# schematic.net
KiCad netlist of a schematic drawn in EasyEDA
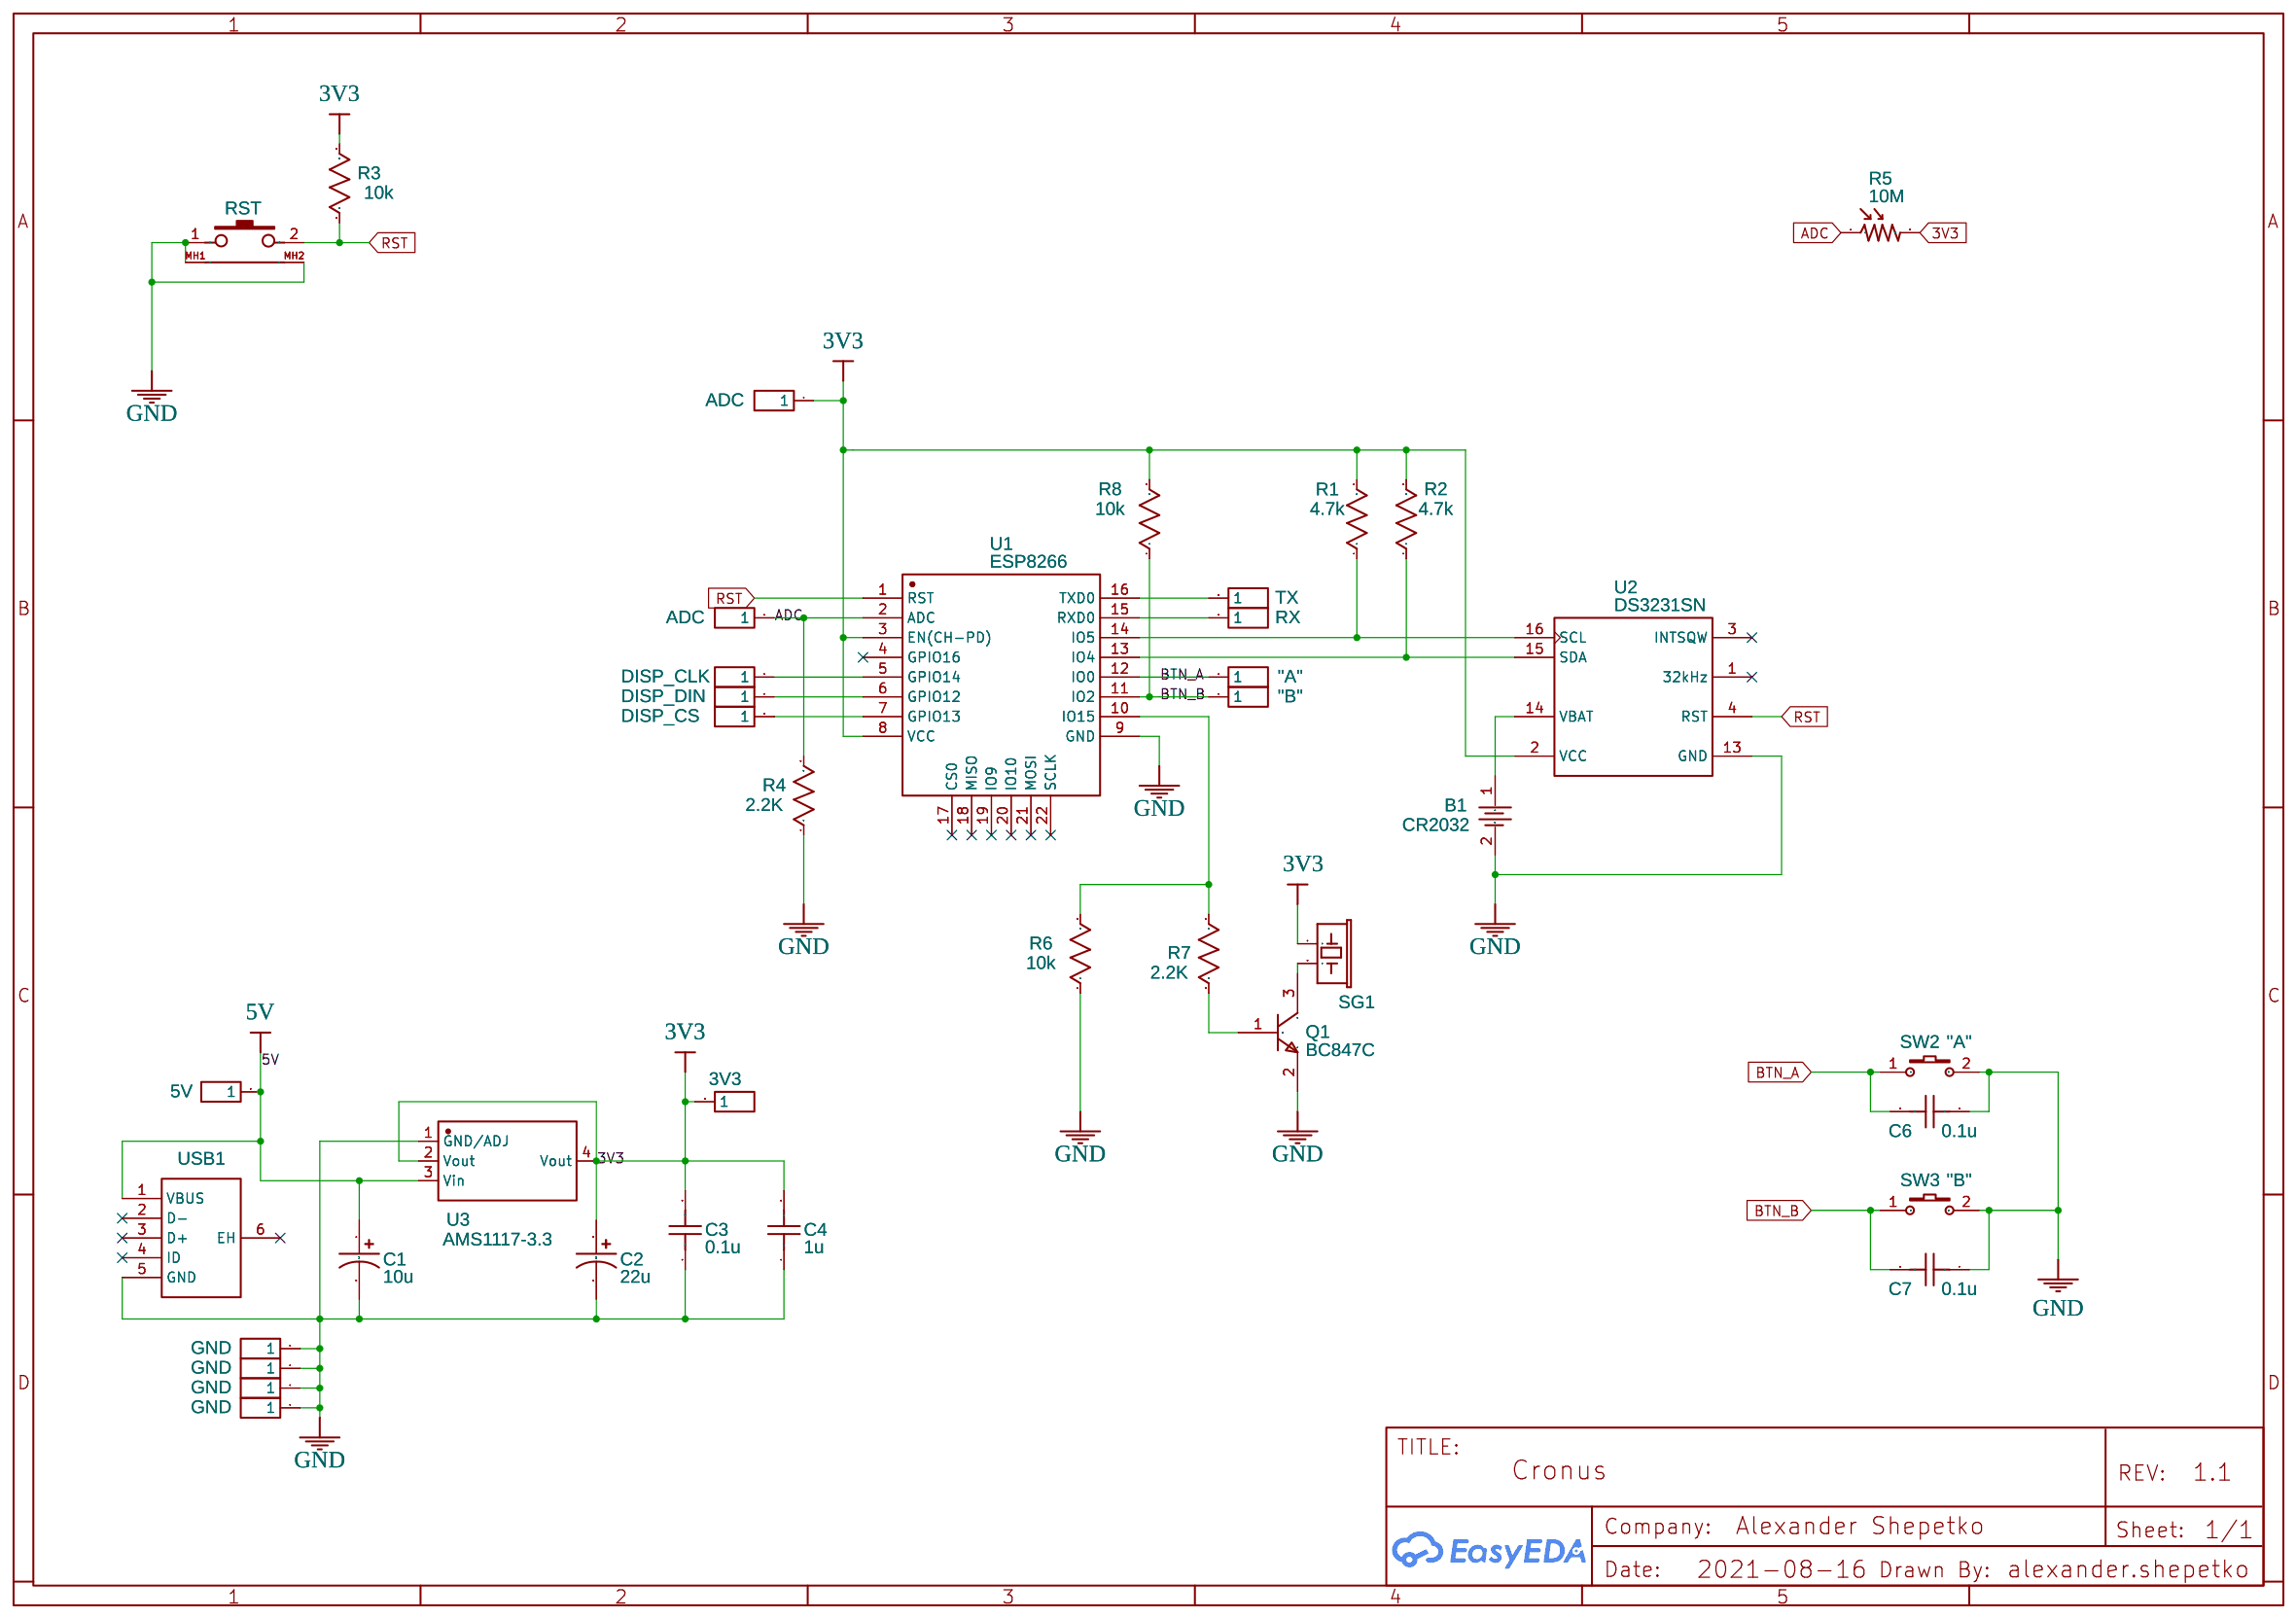
[diagram p0: schematic sheet]

(export (version "E")
  (design (tool "Eeschema 10.0.6"))
  (components
    (comp (ref "B1")
      (value "CR2032")
      (fields (field (name "BOM_Manufacturer Part") "BS-2-1") (field (name "BOM_Supplier Part") "C70376"))
      (libsource (lib "") (part "CR2032-BS-2-1"))
    )
    (comp (ref "C1") (value "10u") (libsource (lib "") (part "C_Tan_SMD_A_US_1")))
    (comp (ref "C2") (value "22u") (libsource (lib "") (part "C_Tan_SMD_A_US")))
    (comp (ref "C3") (value "0.1u") (libsource (lib "") (part "C_0603_US")))
    (comp (ref "C4") (value "1u") (libsource (lib "") (part "C_0603_US")))
    (comp (ref "C6") (value "0.1u") (libsource (lib "") (part "C_0603_US_1")))
    (comp (ref "C7") (value "0.1u") (libsource (lib "") (part "C_0603_US_1")))
    (comp (ref "J1")
      (value "DISP_CLK")
      (fields (field (name "BOM_Supplier Part") "C81276"))
      (libsource (lib "") (part "HDR-M-2.54_1x1_1"))
    )
    (comp (ref "J2")
      (value "DISP_DIN")
      (fields (field (name "BOM_Supplier Part") "C81276"))
      (libsource (lib "") (part "HDR-M-2.54_1x1_1"))
    )
    (comp (ref "J3")
      (value "DISP_CS")
      (fields (field (name "BOM_Supplier Part") "C81276"))
      (libsource (lib "") (part "HDR-M-2.54_1x1_1"))
    )
    (comp (ref "J4")
      (value "\"A\"")
      (fields (field (name "BOM_Supplier Part") "C81276"))
      (libsource (lib "") (part "HDR-M-2.54_1x1"))
    )
    (comp (ref "J5")
      (value "TX")
      (fields (field (name "BOM_Supplier Part") "C81276"))
      (libsource (lib "") (part "HDR-M-2.54_1x1"))
    )
    (comp (ref "J6")
      (value "RX")
      (fields (field (name "BOM_Supplier Part") "C81276"))
      (libsource (lib "") (part "HDR-M-2.54_1x1"))
    )
    (comp (ref "J7")
      (value "\"B\"")
      (fields (field (name "BOM_Supplier Part") "C81276"))
      (libsource (lib "") (part "HDR-M-2.54_1x1"))
    )
    (comp (ref "J8")
      (value "ADC")
      (fields (field (name "BOM_Supplier Part") "C81276"))
      (libsource (lib "") (part "HDR-M-2.54_1x1_1"))
    )
    (comp (ref "J9")
      (value "GND")
      (fields (field (name "BOM_Supplier Part") "C81276"))
      (libsource (lib "") (part "HDR-M-2.54_1x1_1"))
    )
    (comp (ref "J10")
      (value "ADC")
      (fields (field (name "BOM_Supplier Part") "C81276"))
      (libsource (lib "") (part "HDR-M-2.54_1x1_1"))
    )
    (comp (ref "J11")
      (value "GND")
      (fields (field (name "BOM_Supplier Part") "C81276"))
      (libsource (lib "") (part "HDR-M-2.54_1x1_1"))
    )
    (comp (ref "J12")
      (value "5V")
      (fields (field (name "BOM_Supplier Part") "C81276"))
      (libsource (lib "") (part "HDR-M-2.54_1x1_1"))
    )
    (comp (ref "J13")
      (value "GND")
      (fields (field (name "BOM_Supplier Part") "C81276"))
      (libsource (lib "") (part "HDR-M-2.54_1x1_1"))
    )
    (comp (ref "J14")
      (value "GND")
      (fields (field (name "BOM_Supplier Part") "C81276"))
      (libsource (lib "") (part "HDR-M-2.54_1x1_1"))
    )
    (comp (ref "J15")
      (value "3V3")
      (fields (field (name "BOM_Supplier Part") "C81276"))
      (libsource (lib "") (part "HDR-M-2.54_1x1"))
    )
    (comp (ref "Q1") (value "BC847C") (libsource (lib "") (part "BC847CLT3")))
    (comp (ref "R1") (value "4.7k") (libsource (lib "") (part "R_0603_US")))
    (comp (ref "R2") (value "4.7k") (libsource (lib "") (part "R_0603_US")))
    (comp (ref "R3") (value "10k") (libsource (lib "") (part "R_0603_US")))
    (comp (ref "R4") (value "2.2K") (libsource (lib "") (part "R_0603_US")))
    (comp (ref "R5") (value "10M") (libsource (lib "") (part "PHOTORESPDV-P9")))
    (comp (ref "R6") (value "10k") (libsource (lib "") (part "R_0603_US")))
    (comp (ref "R7") (value "2.2K") (libsource (lib "") (part "R_0603_US_1")))
    (comp (ref "R8") (value "10k") (libsource (lib "") (part "R_0603_US")))
    (comp (ref "SG1") (value "BUZZER") (libsource (lib "") (part "BUZZER")))
    (comp (ref "SW1")
      (value "RST")
      (fields
        (field (name "BOM_Manufacturer Part") "Switch,6*6*9Plastic head,260G, 0.25mm,Side bracket")
        (field (name "BOM_Supplier Part") "C71842")
      )
      (libsource (lib "") (part "Button-6x6x9-Right-Angle"))
    )
    (comp (ref "SW2")
      (value "\"A\"")
      (fields
        (field (name "BOM_Manufacturer Part") "K2-1107ST-A4SW-06")
        (field (name "BOM_Supplier Part") "C118141")
      )
      (libsource (lib "") (part "K2-3.6×6.1_SMD"))
    )
    (comp (ref "SW3")
      (value "\"B\"")
      (fields
        (field (name "BOM_Manufacturer Part") "K2-1107ST-A4SW-06")
        (field (name "BOM_Supplier Part") "C118141")
      )
      (libsource (lib "") (part "K2-3.6×6.1_SMD"))
    )
    (comp (ref "U1")
      (value "ESP8266")
      (fields
        (field (name "BOM_Manufacturer Part") "ESP-12F(ESP8266MOD)")
        (field (name "BOM_Supplier Part") "C82891")
      )
      (libsource (lib "") (part "ESP-12F(ESP8266MOD)"))
    )
    (comp (ref "U2")
      (value "DS3231SN")
      (fields (field (name "BOM_Supplier Part") "C9866"))
      (libsource (lib "") (part "DS3231SN#"))
    )
    (comp (ref "U3")
      (value "AMS1117-3.3")
      (fields (field (name "BOM_Supplier Part") "C6186"))
      (libsource (lib "") (part "AMS1117-3.3"))
    )
    (comp (ref "USB1")
      (value "A4A0505-C-30-R")
      (fields (field (name "BOM_Supplier Part") "C694908"))
      (libsource (lib "") (part "A4A0505-C-30-R"))
    )
  )
  (nets
    (net (code "1") (name "3V3") (class "Default")
      (node (ref "C2") (pin "2") (pinfunction "1_2") (pintype "unspecified"))
      (node (ref "C3") (pin "2") (pinfunction "2_2") (pintype "unspecified"))
      (node (ref "C4") (pin "2") (pinfunction "2_2") (pintype "unspecified"))
      (node (ref "J10") (pin "1") (pinfunction "1_1") (pintype "input"))
      (node (ref "J15") (pin "1") (pinfunction "1_1") (pintype "input"))
      (node (ref "R1") (pin "2") (pinfunction "2_2") (pintype "unspecified"))
      (node (ref "R2") (pin "2") (pinfunction "2_2") (pintype "unspecified"))
      (node (ref "R3") (pin "2") (pinfunction "2_2") (pintype "unspecified"))
      (node (ref "R5") (pin "2") (pinfunction "2_2") (pintype "unspecified"))
      (node (ref "R8") (pin "2") (pinfunction "2_2") (pintype "unspecified"))
      (node (ref "SG1") (pin "1") (pinfunction "1_1") (pintype "unspecified"))
      (node (ref "U1") (pin "3") (pinfunction "EN(CH-PD)_3") (pintype "unspecified"))
      (node (ref "U1") (pin "8") (pinfunction "VCC_8") (pintype "unspecified"))
      (node (ref "U2") (pin "2") (pinfunction "VCC_2") (pintype "passive"))
      (node (ref "U3") (pin "2") (pinfunction "Vout_2") (pintype "unspecified"))
      (node (ref "U3") (pin "4") (pinfunction "Vout_4") (pintype "unspecified"))
    )
    (net (code "2") (name "5V") (class "Default")
      (node (ref "C1") (pin "1") (pinfunction "1_1") (pintype "unspecified"))
      (node (ref "J12") (pin "1") (pinfunction "1_1") (pintype "input"))
      (node (ref "U3") (pin "3") (pinfunction "Vin_3") (pintype "unspecified"))
      (node (ref "USB1") (pin "1") (pinfunction "VBUS_1") (pintype "unspecified"))
    )
    (net (code "3") (name "ADC") (class "Default")
      (node (ref "J8") (pin "1") (pinfunction "1_1") (pintype "input"))
      (node (ref "R4") (pin "2") (pinfunction "2_2") (pintype "unspecified"))
      (node (ref "R5") (pin "1") (pinfunction "1_1") (pintype "unspecified"))
      (node (ref "U1") (pin "2") (pinfunction "ADC_2") (pintype "unspecified"))
    )
    (net (code "4") (name "BTN_A") (class "Default")
      (node (ref "C6") (pin "2") (pinfunction "2_2") (pintype "unspecified"))
      (node (ref "J4") (pin "1") (pinfunction "1_1") (pintype "input"))
      (node (ref "SW2") (pin "1") (pinfunction "1_1") (pintype "unspecified"))
      (node (ref "U1") (pin "12") (pinfunction "IO0_12") (pintype "unspecified"))
    )
    (net (code "5") (name "BTN_B") (class "Default")
      (node (ref "C7") (pin "2") (pinfunction "2_2") (pintype "unspecified"))
      (node (ref "J7") (pin "1") (pinfunction "1_1") (pintype "input"))
      (node (ref "R8") (pin "1") (pinfunction "1_1") (pintype "unspecified"))
      (node (ref "SW3") (pin "1") (pinfunction "1_1") (pintype "unspecified"))
      (node (ref "U1") (pin "11") (pinfunction "IO2_11") (pintype "unspecified"))
    )
    (net (code "6") (name "GND") (class "Default")
      (node (ref "B1") (pin "2") (pinfunction "2_2") (pintype "input"))
      (node (ref "C1") (pin "2") (pinfunction "2_2") (pintype "unspecified"))
      (node (ref "C2") (pin "1") (pinfunction "2_1") (pintype "unspecified"))
      (node (ref "C3") (pin "1") (pinfunction "1_1") (pintype "unspecified"))
      (node (ref "C4") (pin "1") (pinfunction "1_1") (pintype "unspecified"))
      (node (ref "C6") (pin "1") (pinfunction "1_1") (pintype "unspecified"))
      (node (ref "C7") (pin "1") (pinfunction "1_1") (pintype "unspecified"))
      (node (ref "J11") (pin "1") (pinfunction "1_1") (pintype "input"))
      (node (ref "J13") (pin "1") (pinfunction "1_1") (pintype "input"))
      (node (ref "J14") (pin "1") (pinfunction "1_1") (pintype "input"))
      (node (ref "J9") (pin "1") (pinfunction "1_1") (pintype "input"))
      (node (ref "Q1") (pin "2") (pinfunction "E_2") (pintype "unspecified"))
      (node (ref "R4") (pin "1") (pinfunction "1_1") (pintype "unspecified"))
      (node (ref "R6") (pin "1") (pinfunction "1_1") (pintype "unspecified"))
      (node (ref "SW1") (pin "1") (pinfunction "1_1") (pintype "input"))
      (node (ref "SW1") (pin "MH1") (pinfunction "MH1_MH1") (pintype "input"))
      (node (ref "SW1") (pin "MH2") (pinfunction "MH2_MH2") (pintype "input"))
      (node (ref "SW2") (pin "2") (pinfunction "2_2") (pintype "unspecified"))
      (node (ref "SW3") (pin "2") (pinfunction "2_2") (pintype "unspecified"))
      (node (ref "U1") (pin "9") (pinfunction "GND_9") (pintype "unspecified"))
      (node (ref "U2") (pin "13") (pinfunction "GND_13") (pintype "passive"))
      (node (ref "U3") (pin "1") (pinfunction "GND/ADJ_1") (pintype "unspecified"))
      (node (ref "USB1") (pin "5") (pinfunction "GND_5") (pintype "unspecified"))
    )
    (net (code "7") (name "Net-(Q1-B)") (class "Default")
      (node (ref "Q1") (pin "1") (pinfunction "B_1") (pintype "unspecified"))
      (node (ref "R7") (pin "2") (pinfunction "2_2") (pintype "unspecified"))
    )
    (net (code "8") (name "Net-(Q1-C)") (class "Default")
      (node (ref "Q1") (pin "3") (pinfunction "C_3") (pintype "unspecified"))
      (node (ref "SG1") (pin "2") (pinfunction "1_2") (pintype "unspecified"))
    )
    (net (code "9") (name "Net-(U1-GPIO12)") (class "Default")
      (node (ref "J2") (pin "1") (pinfunction "1_1") (pintype "input"))
      (node (ref "U1") (pin "6") (pinfunction "GPIO12_6") (pintype "unspecified"))
    )
    (net (code "10") (name "Net-(U1-GPIO13)") (class "Default")
      (node (ref "J3") (pin "1") (pinfunction "1_1") (pintype "input"))
      (node (ref "U1") (pin "7") (pinfunction "GPIO13_7") (pintype "unspecified"))
    )
    (net (code "11") (name "Net-(U1-GPIO14)") (class "Default")
      (node (ref "J1") (pin "1") (pinfunction "1_1") (pintype "input"))
      (node (ref "U1") (pin "5") (pinfunction "GPIO14_5") (pintype "unspecified"))
    )
    (net (code "12") (name "Net-(U1-IO4)") (class "Default")
      (node (ref "R2") (pin "1") (pinfunction "1_1") (pintype "unspecified"))
      (node (ref "U1") (pin "13") (pinfunction "IO4_13") (pintype "unspecified"))
      (node (ref "U2") (pin "15") (pinfunction "SDA_15") (pintype "bidirectional"))
    )
    (net (code "13") (name "Net-(U1-IO5)") (class "Default")
      (node (ref "R1") (pin "1") (pinfunction "1_1") (pintype "unspecified"))
      (node (ref "U1") (pin "14") (pinfunction "IO5_14") (pintype "unspecified"))
      (node (ref "U2") (pin "16") (pinfunction "SCL_16") (pintype "unspecified"))
    )
    (net (code "14") (name "Net-(U1-IO15)") (class "Default")
      (node (ref "R6") (pin "2") (pinfunction "2_2") (pintype "unspecified"))
      (node (ref "R7") (pin "1") (pinfunction "1_1") (pintype "unspecified"))
      (node (ref "U1") (pin "10") (pinfunction "IO15_10") (pintype "unspecified"))
    )
    (net (code "15") (name "Net-(U1-RXD0)") (class "Default")
      (node (ref "J6") (pin "1") (pinfunction "1_1") (pintype "input"))
      (node (ref "U1") (pin "15") (pinfunction "RXD0_15") (pintype "unspecified"))
    )
    (net (code "16") (name "Net-(U1-TXD0)") (class "Default")
      (node (ref "J5") (pin "1") (pinfunction "1_1") (pintype "input"))
      (node (ref "U1") (pin "16") (pinfunction "TXD0_16") (pintype "unspecified"))
    )
    (net (code "17") (name "Net-(U2-VBAT)") (class "Default")
      (node (ref "B1") (pin "1") (pinfunction "1_1") (pintype "input"))
      (node (ref "U2") (pin "14") (pinfunction "VBAT_14") (pintype "passive"))
    )
    (net (code "18") (name "RST") (class "Default")
      (node (ref "R3") (pin "1") (pinfunction "1_1") (pintype "unspecified"))
      (node (ref "SW1") (pin "2") (pinfunction "2_2") (pintype "input"))
      (node (ref "U1") (pin "1") (pinfunction "RST_1") (pintype "unspecified"))
      (node (ref "U2") (pin "4") (pinfunction "RST_4") (pintype "bidirectional"))
    )
    (net (code "19") (name "unconnected-(U1-CS0-Pad17)") (class "Default")
      (node (ref "U1") (pin "17") (pinfunction "CS0_17") (pintype "unspecified+no_connect"))
    )
    (net (code "20") (name "unconnected-(U1-GPIO16-Pad4)") (class "Default")
      (node (ref "U1") (pin "4") (pinfunction "GPIO16_4") (pintype "unspecified+no_connect"))
    )
    (net (code "21") (name "unconnected-(U1-IO9-Pad19)") (class "Default")
      (node (ref "U1") (pin "19") (pinfunction "IO9_19") (pintype "unspecified+no_connect"))
    )
    (net (code "22") (name "unconnected-(U1-IO10-Pad20)") (class "Default")
      (node (ref "U1") (pin "20") (pinfunction "IO10_20") (pintype "unspecified+no_connect"))
    )
    (net (code "23") (name "unconnected-(U1-MISO-Pad18)") (class "Default")
      (node (ref "U1") (pin "18") (pinfunction "MISO_18") (pintype "unspecified+no_connect"))
    )
    (net (code "24") (name "unconnected-(U1-MOSI-Pad21)") (class "Default")
      (node (ref "U1") (pin "21") (pinfunction "MOSI_21") (pintype "unspecified+no_connect"))
    )
    (net (code "25") (name "unconnected-(U1-SCLK-Pad22)") (class "Default")
      (node (ref "U1") (pin "22") (pinfunction "SCLK_22") (pintype "unspecified+no_connect"))
    )
    (net (code "26") (name "unconnected-(U2-32kHz-Pad1)") (class "Default")
      (node (ref "U2") (pin "1") (pinfunction "32kHz_1") (pintype "unspecified+no_connect"))
    )
    (net (code "27") (name "unconnected-(U2-INTSQW-Pad3)") (class "Default")
      (node (ref "U2") (pin "3") (pinfunction "INTSQW_3") (pintype "unspecified+no_connect"))
    )
    (net (code "28") (name "unconnected-(USB1-D+-Pad3)") (class "Default")
      (node (ref "USB1") (pin "3") (pinfunction "D+_3") (pintype "unspecified+no_connect"))
    )
    (net (code "29") (name "unconnected-(USB1-D--Pad2)") (class "Default")
      (node (ref "USB1") (pin "2") (pinfunction "D-_2") (pintype "unspecified+no_connect"))
    )
    (net (code "30") (name "unconnected-(USB1-EH-Pad6)") (class "Default")
      (node (ref "USB1") (pin "6") (pinfunction "EH_6") (pintype "unspecified+no_connect"))
    )
    (net (code "31") (name "unconnected-(USB1-ID-Pad4)") (class "Default")
      (node (ref "USB1") (pin "4") (pinfunction "ID_4") (pintype "unspecified+no_connect"))
    )
  )
)
